# Snowman.net
KiCad netlist of a schematic drawn in EAGLE
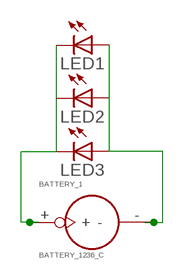
[diagram p0: schematic, sheet 1]

(export (version "E")
  (design (tool "Eeschema 10.0.6"))
  (components
    (comp (ref "BATTERY_1")
      (value "BATTERY_1236_C")
      (footprint "eagle-import:BATTERY_1236_C")
      (libsource (lib "eagle-import") (part "BATTERY_1236_C"))
    )
    (comp (ref "LED1")
      (value "LED5MM")
      (footprint "eagle-import:LED5MM")
      (libsource (lib "eagle-import") (part "LED5MM"))
    )
    (comp (ref "LED2")
      (value "LED5MM")
      (footprint "eagle-import:LED5MM")
      (libsource (lib "eagle-import") (part "LED5MM"))
    )
    (comp (ref "LED3")
      (value "LED5MM")
      (footprint "eagle-import:LED5MM")
      (libsource (lib "eagle-import") (part "LED5MM"))
    )
  )
  (nets
    (net (code "1") (name "Net-(BATTERY_1-Pad-)") (class "Default")
      (node (ref "BATTERY_1") (pin "-") (pinfunction "-_-") (pintype "bidirectional"))
      (node (ref "LED1") (pin "A") (pinfunction "A_A") (pintype "passive"))
      (node (ref "LED2") (pin "A") (pinfunction "A_A") (pintype "passive"))
      (node (ref "LED3") (pin "A") (pinfunction "A_A") (pintype "passive"))
    )
    (net (code "2") (name "Net-(LED1-C)") (class "Default")
      (node (ref "BATTERY_1") (pin "+") (pinfunction "+_+") (pintype "bidirectional"))
      (node (ref "LED1") (pin "K") (pinfunction "C_K") (pintype "passive"))
      (node (ref "LED2") (pin "K") (pinfunction "C_K") (pintype "passive"))
      (node (ref "LED3") (pin "K") (pinfunction "C_K") (pintype "passive"))
    )
  )
)
